# design.net
KiCad netlist of a schematic drawn in Altium Designer
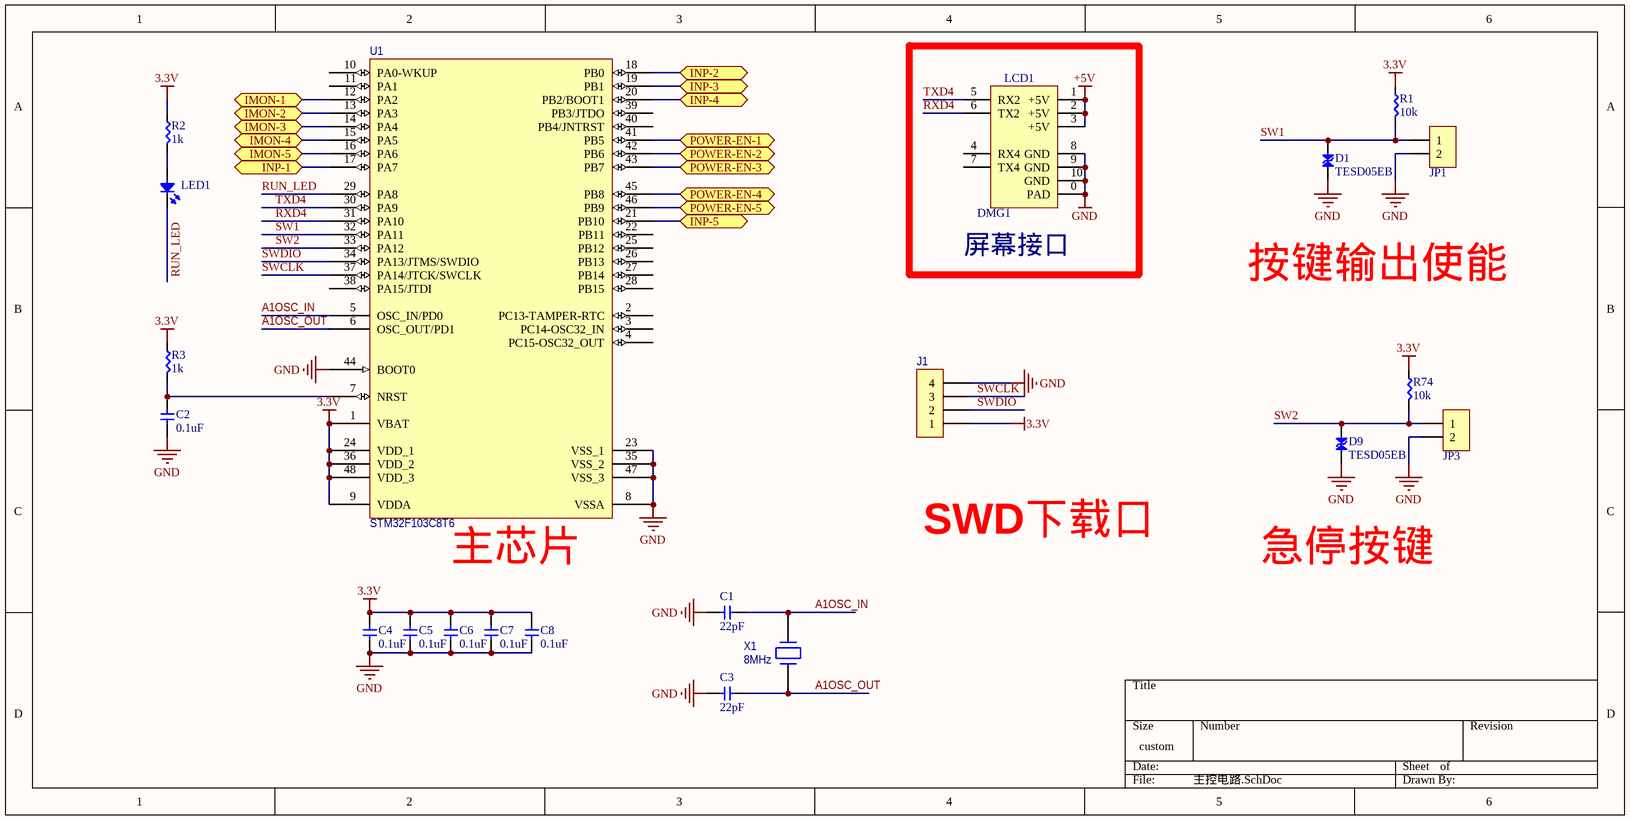
[diagram p0: 主控电路.SchDoc]

(export (version "E")
  (design (tool "Eeschema 10.0.6"))
  (components
    (comp (ref "C1") (value "22pF") (footprint "C 0603_M") (libsource (lib "史福祥库") (part "C")))
    (comp (ref "C2") (value "0.1uF") (footprint "C 0603_M") (libsource (lib "史福祥库") (part "C")))
    (comp (ref "C3") (value "22pF") (footprint "C 0603_M") (libsource (lib "史福祥库") (part "C")))
    (comp (ref "C4") (value "0.1uF") (footprint "C 0603_M") (libsource (lib "史福祥库") (part "C")))
    (comp (ref "C5") (value "0.1uF") (footprint "C 0603_M") (libsource (lib "史福祥库") (part "C")))
    (comp (ref "C6") (value "0.1uF") (footprint "C 0603_M") (libsource (lib "史福祥库") (part "C")))
    (comp (ref "C7") (value "0.1uF") (footprint "C 0603_M") (libsource (lib "史福祥库") (part "C")))
    (comp (ref "C8") (value "0.1uF") (footprint "C 0603_M") (libsource (lib "史福祥库") (part "C")))
    (comp (ref "D1")
      (value "TESD05EB")
      (footprint "0603-ESD")
      (fields (field (name "PUBLISHER") "Altium Limited"))
      (libsource (lib "史福祥库") (part "D  TVS"))
    )
    (comp (ref "D9")
      (value "TESD05EB")
      (footprint "0603-ESD")
      (fields (field (name "PUBLISHER") "Altium Limited"))
      (libsource (lib "史福祥库") (part "D  TVS"))
    )
    (comp (ref "DMG1") (value "LCD1") (footprint "FCC1.0*10") (libsource (lib "YYL") (part "DMG48480C040")))
    (comp (ref "J1")
      (value "swio")
      (footprint "HDR2.54-LI-4P")
      (description "Connector")
      (libsource (lib "General") (part "HDR1x4"))
    )
    (comp (ref "JP1")
      (value "HDR-1X2")
      (footprint "XH2.54-LI-2P")
      (description "2P接插件")
      (fields (field (name "版权归属") "源创客"))
      (libsource (lib "4.3   - 接插件-脚距1.5") (part "Header 2"))
    )
    (comp (ref "JP3")
      (value "HDR-1X2")
      (footprint "XH2.54-LI-2P")
      (description "2P接插件")
      (fields (field (name "版权归属") "源创客"))
      (libsource (lib "4.3   - 接插件-脚距1.5") (part "Header 2"))
    )
    (comp (ref "LED1")
      (value "LED")
      (footprint "LED 0603G")
      (fields (field (name "PUBLISHER") "Altium Limited"))
      (libsource (lib "史福祥库") (part "LED"))
    )
    (comp (ref "R1") (value "10k") (footprint "R 0603_M") (libsource (lib "史福祥库") (part "Res")))
    (comp (ref "R2") (value "1k") (footprint "R 0603_M") (libsource (lib "史福祥库") (part "Res")))
    (comp (ref "R3") (value "1k") (footprint "R 0603_M") (libsource (lib "史福祥库") (part "Res")))
    (comp (ref "R74") (value "10k") (footprint "R 0603_M") (libsource (lib "史福祥库") (part "Res")))
    (comp (ref "U1")
      (value "STM32F103C8T6")
      (footprint "LQFP48 7X7_M")
      (description "STM32 ARM-based 32-bit MCU with 128 Kbytes Flash, 48-pin LQFP, Industrial Temperature")
      (fields (field (name "PUBLISHER") "Altium Limited"))
      (libsource (lib "Stimulator") (part "STM32F103CBT6"))
    )
    (comp (ref "X1")
      (value "8MHz")
      (footprint "OSC HC-49SMD")
      (description "Crystal")
      (libsource (lib "*") (part "CRYSTAL"))
    )
  )
  (nets
    (net (code "1") (name "+5V") (class "Default")
      (node (ref "DMG1") (pin "1") (pinfunction "+5V_1") (pintype "passive"))
      (node (ref "DMG1") (pin "2") (pinfunction "+5V_2") (pintype "passive"))
      (node (ref "DMG1") (pin "3") (pinfunction "+5V_3") (pintype "passive"))
    )
    (net (code "2") (name "/A1OSC_IN") (class "Default")
      (node (ref "C1") (pin "1") (pinfunction "1_1") (pintype "passive"))
      (node (ref "U1") (pin "5") (pinfunction "OSC_IN/PD0_5") (pintype "passive"))
      (node (ref "X1") (pin "2") (pinfunction "2_2") (pintype "passive"))
    )
    (net (code "3") (name "/A1OSC_OUT") (class "Default")
      (node (ref "C3") (pin "1") (pinfunction "1_1") (pintype "passive"))
      (node (ref "U1") (pin "6") (pinfunction "OSC_OUT/PD1_6") (pintype "passive"))
      (node (ref "X1") (pin "1") (pinfunction "1_1") (pintype "passive"))
    )
    (net (code "4") (name "/IMON-1") (class "Default")
      (node (ref "U1") (pin "12") (pinfunction "PA2_12") (pintype "bidirectional"))
    )
    (net (code "5") (name "/IMON-2") (class "Default")
      (node (ref "U1") (pin "13") (pinfunction "PA3_13") (pintype "bidirectional"))
    )
    (net (code "6") (name "/IMON-3") (class "Default")
      (node (ref "U1") (pin "14") (pinfunction "PA4_14") (pintype "bidirectional"))
    )
    (net (code "7") (name "/IMON-4") (class "Default")
      (node (ref "U1") (pin "15") (pinfunction "PA5_15") (pintype "bidirectional"))
    )
    (net (code "8") (name "/IMON-5") (class "Default")
      (node (ref "U1") (pin "16") (pinfunction "PA6_16") (pintype "bidirectional"))
    )
    (net (code "9") (name "/INP-1") (class "Default")
      (node (ref "U1") (pin "17") (pinfunction "PA7_17") (pintype "bidirectional"))
    )
    (net (code "10") (name "/INP-2") (class "Default")
      (node (ref "U1") (pin "18") (pinfunction "PB0_18") (pintype "bidirectional"))
    )
    (net (code "11") (name "/INP-3") (class "Default")
      (node (ref "U1") (pin "19") (pinfunction "PB1_19") (pintype "bidirectional"))
    )
    (net (code "12") (name "/INP-4") (class "Default")
      (node (ref "U1") (pin "20") (pinfunction "PB2/BOOT1_20") (pintype "bidirectional"))
    )
    (net (code "13") (name "/INP-5") (class "Default")
      (node (ref "U1") (pin "21") (pinfunction "PB10_21") (pintype "bidirectional"))
    )
    (net (code "14") (name "/POWER-EN-1") (class "Default")
      (node (ref "U1") (pin "41") (pinfunction "PB5_41") (pintype "bidirectional"))
    )
    (net (code "15") (name "/POWER-EN-2") (class "Default")
      (node (ref "U1") (pin "42") (pinfunction "PB6_42") (pintype "bidirectional"))
    )
    (net (code "16") (name "/POWER-EN-3") (class "Default")
      (node (ref "U1") (pin "43") (pinfunction "PB7_43") (pintype "bidirectional"))
    )
    (net (code "17") (name "/POWER-EN-4") (class "Default")
      (node (ref "U1") (pin "45") (pinfunction "PB8_45") (pintype "bidirectional"))
    )
    (net (code "18") (name "/POWER-EN-5") (class "Default")
      (node (ref "U1") (pin "46") (pinfunction "PB9_46") (pintype "bidirectional"))
    )
    (net (code "19") (name "/RUN_LED") (class "Default")
      (node (ref "LED1") (pin "2") (pinfunction "K_2") (pintype "passive"))
      (node (ref "U1") (pin "29") (pinfunction "PA8_29") (pintype "bidirectional"))
    )
    (net (code "20") (name "/RXD4") (class "Default")
      (node (ref "DMG1") (pin "6") (pinfunction "TX2_6") (pintype "passive"))
      (node (ref "U1") (pin "31") (pinfunction "PA10_31") (pintype "bidirectional"))
    )
    (net (code "21") (name "/SW1") (class "Default")
      (node (ref "D1") (pin "2") (pinfunction "K_2") (pintype "passive"))
      (node (ref "JP1") (pin "1") (pinfunction "1_1") (pintype "passive"))
      (node (ref "R1") (pin "2") (pinfunction "2_2") (pintype "passive"))
      (node (ref "U1") (pin "32") (pinfunction "PA11_32") (pintype "bidirectional"))
    )
    (net (code "22") (name "/SW2") (class "Default")
      (node (ref "D9") (pin "2") (pinfunction "K_2") (pintype "passive"))
      (node (ref "JP3") (pin "1") (pinfunction "1_1") (pintype "passive"))
      (node (ref "R74") (pin "2") (pinfunction "2_2") (pintype "passive"))
      (node (ref "U1") (pin "33") (pinfunction "PA12_33") (pintype "bidirectional"))
    )
    (net (code "23") (name "/SWCLK") (class "Default")
      (node (ref "J1") (pin "3") (pinfunction "3_3") (pintype "passive"))
      (node (ref "U1") (pin "37") (pinfunction "PA14/JTCK/SWCLK_37") (pintype "bidirectional"))
    )
    (net (code "24") (name "/SWDIO") (class "Default")
      (node (ref "J1") (pin "2") (pinfunction "2_2") (pintype "passive"))
      (node (ref "U1") (pin "34") (pinfunction "PA13/JTMS/SWDIO_34") (pintype "bidirectional"))
    )
    (net (code "25") (name "/TXD4") (class "Default")
      (node (ref "DMG1") (pin "5") (pinfunction "RX2_5") (pintype "passive"))
      (node (ref "U1") (pin "30") (pinfunction "PA9_30") (pintype "bidirectional"))
    )
    (net (code "26") (name "3.3V") (class "Default")
      (node (ref "C4") (pin "2") (pinfunction "2_2") (pintype "passive"))
      (node (ref "C5") (pin "2") (pinfunction "2_2") (pintype "passive"))
      (node (ref "C6") (pin "2") (pinfunction "2_2") (pintype "passive"))
      (node (ref "C7") (pin "2") (pinfunction "2_2") (pintype "passive"))
      (node (ref "C8") (pin "2") (pinfunction "2_2") (pintype "passive"))
      (node (ref "J1") (pin "1") (pinfunction "1_1") (pintype "passive"))
      (node (ref "R1") (pin "1") (pinfunction "1_1") (pintype "passive"))
      (node (ref "R2") (pin "1") (pinfunction "1_1") (pintype "passive"))
      (node (ref "R3") (pin "1") (pinfunction "1_1") (pintype "passive"))
      (node (ref "R74") (pin "1") (pinfunction "1_1") (pintype "passive"))
      (node (ref "U1") (pin "1") (pinfunction "VBAT_1") (pintype "power_in"))
      (node (ref "U1") (pin "24") (pinfunction "VDD_1_24") (pintype "power_in"))
      (node (ref "U1") (pin "36") (pinfunction "VDD_2_36") (pintype "power_in"))
      (node (ref "U1") (pin "48") (pinfunction "VDD_3_48") (pintype "power_in"))
      (node (ref "U1") (pin "9") (pinfunction "VDDA_9") (pintype "power_in"))
    )
    (net (code "27") (name "GND") (class "Default")
      (node (ref "C1") (pin "2") (pinfunction "2_2") (pintype "passive"))
      (node (ref "C2") (pin "1") (pinfunction "1_1") (pintype "passive"))
      (node (ref "C3") (pin "2") (pinfunction "2_2") (pintype "passive"))
      (node (ref "C4") (pin "1") (pinfunction "1_1") (pintype "passive"))
      (node (ref "C5") (pin "1") (pinfunction "1_1") (pintype "passive"))
      (node (ref "C6") (pin "1") (pinfunction "1_1") (pintype "passive"))
      (node (ref "C7") (pin "1") (pinfunction "1_1") (pintype "passive"))
      (node (ref "C8") (pin "1") (pinfunction "1_1") (pintype "passive"))
      (node (ref "D1") (pin "1") (pinfunction "A_1") (pintype "passive"))
      (node (ref "D9") (pin "1") (pinfunction "A_1") (pintype "passive"))
      (node (ref "DMG1") (pin "0") (pinfunction "PAD_0") (pintype "passive"))
      (node (ref "DMG1") (pin "10") (pinfunction "GND_10") (pintype "passive"))
      (node (ref "DMG1") (pin "8") (pinfunction "GND_8") (pintype "passive"))
      (node (ref "DMG1") (pin "9") (pinfunction "GND_9") (pintype "passive"))
      (node (ref "J1") (pin "4") (pinfunction "4_4") (pintype "passive"))
      (node (ref "JP1") (pin "2") (pinfunction "2_2") (pintype "passive"))
      (node (ref "JP3") (pin "2") (pinfunction "2_2") (pintype "passive"))
      (node (ref "U1") (pin "23") (pinfunction "VSS_1_23") (pintype "power_in"))
      (node (ref "U1") (pin "35") (pinfunction "VSS_2_35") (pintype "power_in"))
      (node (ref "U1") (pin "44") (pinfunction "BOOT0_44") (pintype "input"))
      (node (ref "U1") (pin "47") (pinfunction "VSS_3_47") (pintype "power_in"))
      (node (ref "U1") (pin "8") (pinfunction "VSSA_8") (pintype "power_in"))
    )
    (net (code "28") (name "Net-(LED1-A)") (class "Default")
      (node (ref "LED1") (pin "1") (pinfunction "A_1") (pintype "passive"))
      (node (ref "R2") (pin "2") (pinfunction "2_2") (pintype "passive"))
    )
    (net (code "29") (name "Net-(U1-NRST)") (class "Default")
      (node (ref "C2") (pin "2") (pinfunction "2_2") (pintype "passive"))
      (node (ref "R3") (pin "2") (pinfunction "2_2") (pintype "passive"))
      (node (ref "U1") (pin "7") (pinfunction "NRST_7") (pintype "bidirectional"))
    )
    (net (code "30") (name "unconnected-(DMG1-RX4-Pad4)") (class "Default")
      (node (ref "DMG1") (pin "4") (pinfunction "RX4_4") (pintype "passive"))
    )
    (net (code "31") (name "unconnected-(DMG1-TX4-Pad7)") (class "Default")
      (node (ref "DMG1") (pin "7") (pinfunction "TX4_7") (pintype "passive"))
    )
    (net (code "32") (name "unconnected-(U1-PA0-WKUP-Pad10)") (class "Default")
      (node (ref "U1") (pin "10") (pinfunction "PA0-WKUP_10") (pintype "bidirectional"))
    )
    (net (code "33") (name "unconnected-(U1-PA1-Pad11)") (class "Default")
      (node (ref "U1") (pin "11") (pinfunction "PA1_11") (pintype "bidirectional"))
    )
    (net (code "34") (name "unconnected-(U1-PA15{slash}JTDI-Pad38)") (class "Default")
      (node (ref "U1") (pin "38") (pinfunction "PA15/JTDI_38") (pintype "bidirectional"))
    )
    (net (code "35") (name "unconnected-(U1-PB3{slash}JTDO-Pad39)") (class "Default")
      (node (ref "U1") (pin "39") (pinfunction "PB3/JTDO_39") (pintype "bidirectional"))
    )
    (net (code "36") (name "unconnected-(U1-PB4{slash}JNTRST-Pad40)") (class "Default")
      (node (ref "U1") (pin "40") (pinfunction "PB4/JNTRST_40") (pintype "bidirectional"))
    )
    (net (code "37") (name "unconnected-(U1-PB11-Pad22)") (class "Default")
      (node (ref "U1") (pin "22") (pinfunction "PB11_22") (pintype "bidirectional"))
    )
    (net (code "38") (name "unconnected-(U1-PB12-Pad25)") (class "Default")
      (node (ref "U1") (pin "25") (pinfunction "PB12_25") (pintype "bidirectional"))
    )
    (net (code "39") (name "unconnected-(U1-PB13-Pad26)") (class "Default")
      (node (ref "U1") (pin "26") (pinfunction "PB13_26") (pintype "bidirectional"))
    )
    (net (code "40") (name "unconnected-(U1-PB14-Pad27)") (class "Default")
      (node (ref "U1") (pin "27") (pinfunction "PB14_27") (pintype "bidirectional"))
    )
    (net (code "41") (name "unconnected-(U1-PB15-Pad28)") (class "Default")
      (node (ref "U1") (pin "28") (pinfunction "PB15_28") (pintype "bidirectional"))
    )
    (net (code "42") (name "unconnected-(U1-PC13-TAMPER-RTC-Pad2)") (class "Default")
      (node (ref "U1") (pin "2") (pinfunction "PC13-TAMPER-RTC_2") (pintype "bidirectional"))
    )
    (net (code "43") (name "unconnected-(U1-PC14-OSC32_IN-Pad3)") (class "Default")
      (node (ref "U1") (pin "3") (pinfunction "PC14-OSC32_IN_3") (pintype "bidirectional"))
    )
    (net (code "44") (name "unconnected-(U1-PC15-OSC32_OUT-Pad4)") (class "Default")
      (node (ref "U1") (pin "4") (pinfunction "PC15-OSC32_OUT_4") (pintype "bidirectional"))
    )
  )
)
